# electrodes.net
KiCad netlist of a schematic drawn in Altium Designer
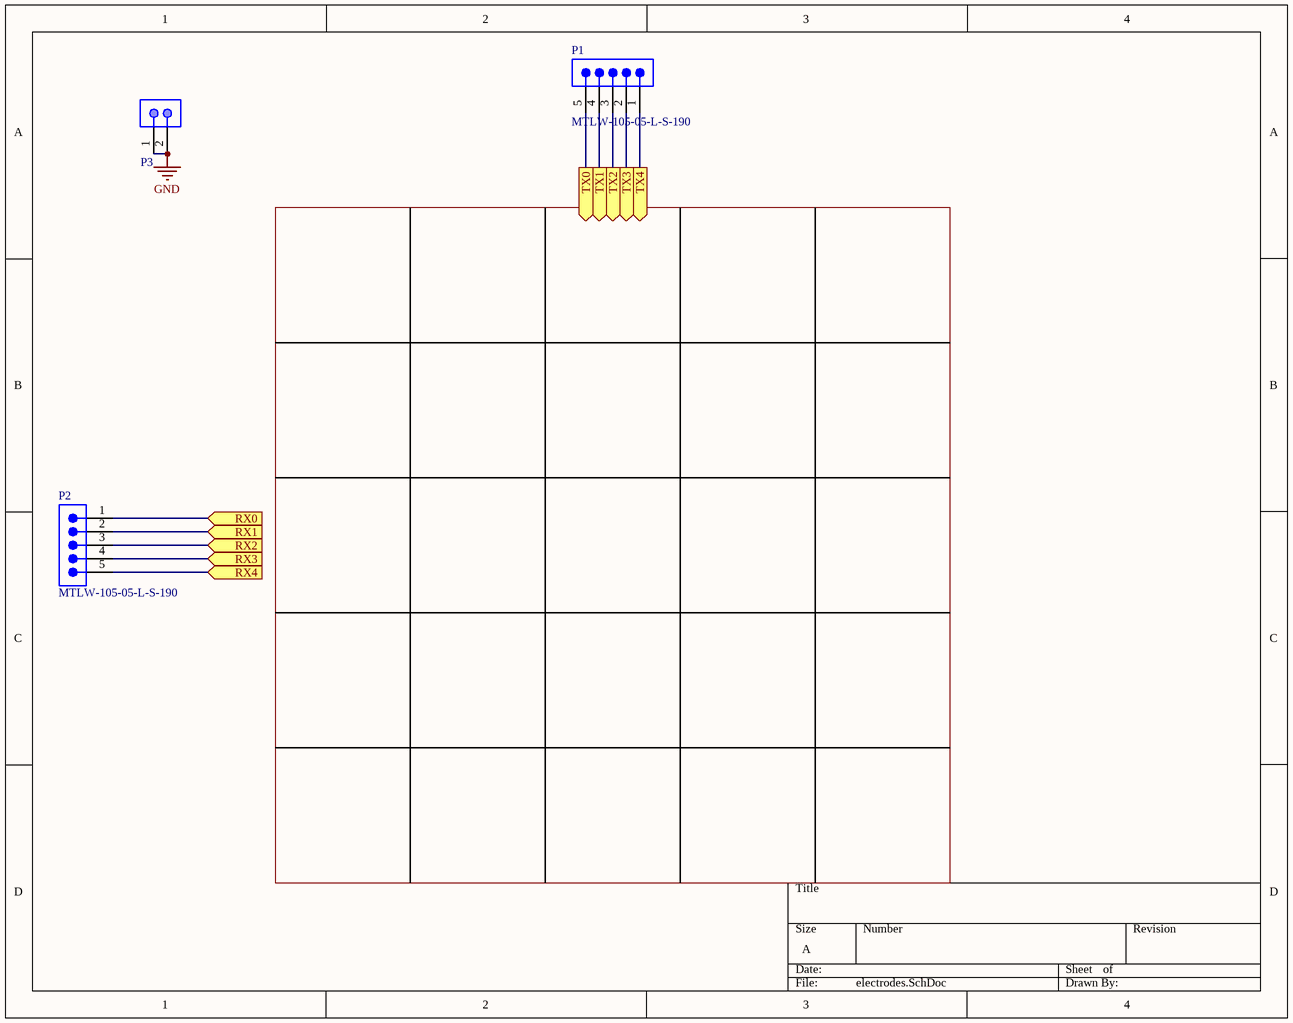
[diagram p0: electrodes.SchDoc]

(export (version "E")
  (design (tool "Eeschema 10.0.6"))
  (components
    (comp (ref "P1")
      (value "MTLW-105-05-L-S-190")
      (footprint "SMTC-MTLW-105-05-X-S-190")
      (fields (field (name "MANUFACTURER") "Samtec"))
      (libsource (lib "Altium Content Vault") (part "SMTC-MTLW-105-05-X-S-190"))
    )
    (comp (ref "P2")
      (value "MTLW-105-05-L-S-190")
      (footprint "SMTC-MTLW-105-05-X-S-190")
      (fields (field (name "MANUFACTURER") "Samtec"))
      (libsource (lib "Altium Content Vault") (part "SMTC-MTLW-105-05-X-S-190"))
    )
    (comp (ref "P3")
      (value "613 002 111 21")
      (footprint "WE-61300211121_V")
      (fields (field (name "MANUFACTURER") "Wuerth Elektronik"))
      (libsource (lib "Altium Content Vault") (part "CN-1P-M-R2"))
    )
  )
  (nets
    (net (code "1") (name "/RX0") (class "Default")
      (node (ref "P2") (pin "1") (pinfunction "1_1") (pintype "passive"))
    )
    (net (code "2") (name "/RX1") (class "Default")
      (node (ref "P2") (pin "2") (pinfunction "2_2") (pintype "passive"))
    )
    (net (code "3") (name "/RX2") (class "Default")
      (node (ref "P2") (pin "3") (pinfunction "3_3") (pintype "passive"))
    )
    (net (code "4") (name "/RX3") (class "Default")
      (node (ref "P2") (pin "4") (pinfunction "4_4") (pintype "passive"))
    )
    (net (code "5") (name "/RX4") (class "Default")
      (node (ref "P2") (pin "5") (pinfunction "5_5") (pintype "passive"))
    )
    (net (code "6") (name "/TX0") (class "Default")
      (node (ref "P1") (pin "5") (pinfunction "5_5") (pintype "passive"))
    )
    (net (code "7") (name "/TX1") (class "Default")
      (node (ref "P1") (pin "4") (pinfunction "4_4") (pintype "passive"))
    )
    (net (code "8") (name "/TX2") (class "Default")
      (node (ref "P1") (pin "3") (pinfunction "3_3") (pintype "passive"))
    )
    (net (code "9") (name "/TX3") (class "Default")
      (node (ref "P1") (pin "2") (pinfunction "2_2") (pintype "passive"))
    )
    (net (code "10") (name "/TX4") (class "Default")
      (node (ref "P1") (pin "1") (pinfunction "1_1") (pintype "passive"))
    )
    (net (code "11") (name "GND") (class "Default")
      (node (ref "P3") (pin "1") (pinfunction "1_1") (pintype "passive"))
      (node (ref "P3") (pin "2") (pinfunction "2_2") (pintype "passive"))
    )
  )
)
